# sammy-schematic.net
KiCad netlist of a schematic drawn in EasyEDA
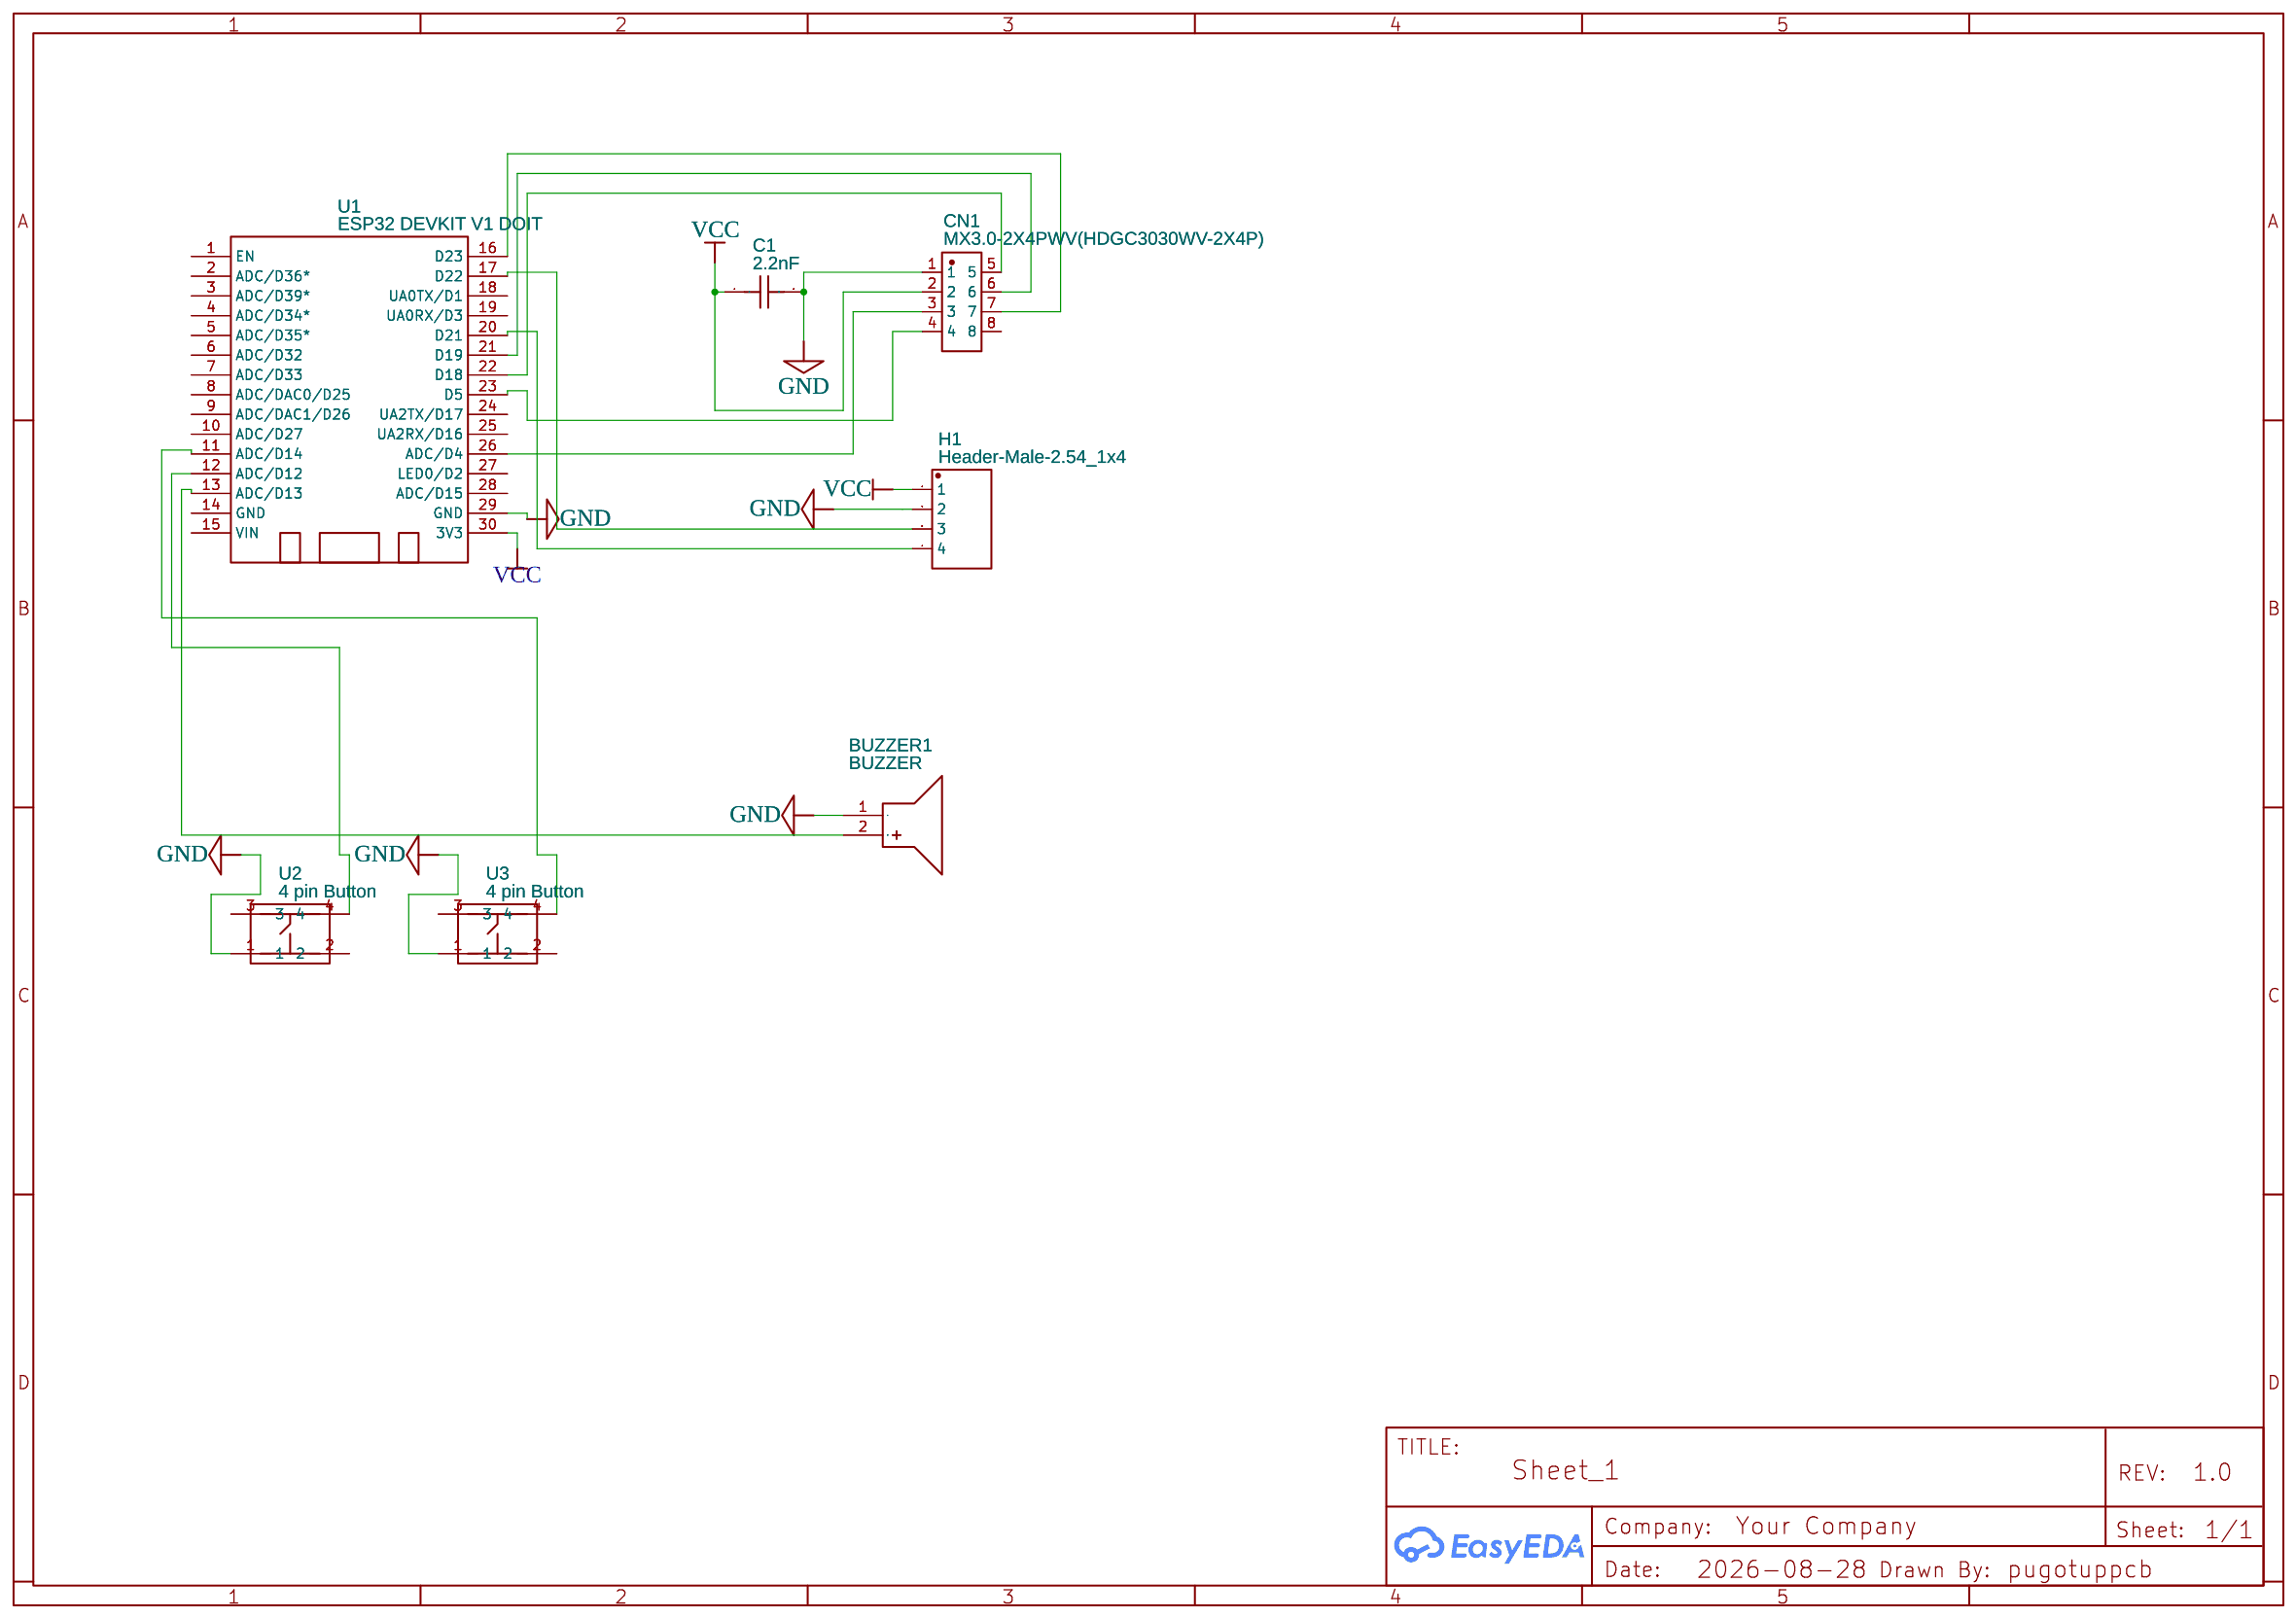
[diagram p0: schematic sheet]

(export (version "E")
  (design (tool "Eeschema 10.0.6"))
  (components
    (comp (ref "BUZZER1")
      (value "BUZZER")
      (fields (field (name "Manufacturer Part") "buzzer"))
      (libsource (lib "") (part "BUZZER"))
    )
    (comp (ref "C1")
      (value "2.2nF")
      (fields (field (name "Manufacturer Part") "C320C222F1G5TA") (field (name "Manufacturer") "KEMET(基美)"))
      (libsource (lib "") (part "C320C222F1G5TA"))
    )
    (comp (ref "CN1")
      (value "MX3.0-2X4PWV(HDGC3030WV-2X4P)")
      (fields (field (name "Manufacturer") "HDGC(华德共创)"))
      (libsource (lib "") (part "MX3.0-2X4PWV(HDGC3030WV-2X4P)"))
    )
    (comp (ref "H1")
      (value "Header-Male-2.54_1x4")
      (fields (field (name "Manufacturer Part") "B-2100S04P-A110") (field (name "Manufacturer") "Ckmtw(灿科盟)"))
      (libsource (lib "") (part "Header-Male-2.54_1x4"))
    )
    (comp (ref "U1") (value "ESP32 DEVKIT V1 DOIT") (libsource (lib "") (part "ESP32 DEVKIT V1 DOIT")))
    (comp (ref "U2") (value "4 pin Button") (libsource (lib "") (part "4 pin Button")))
    (comp (ref "U3") (value "4 pin Button") (libsource (lib "") (part "4 pin Button")))
  )
  (nets
    (net (code "1") (name "GND") (class "Default")
      (node (ref "BUZZER1") (pin "1") (pinfunction "-_1") (pintype "unspecified"))
      (node (ref "C1") (pin "2") (pinfunction "2_2") (pintype "unspecified"))
      (node (ref "CN1") (pin "1") (pinfunction "1_1") (pintype "unspecified"))
      (node (ref "H1") (pin "2") (pinfunction "2_2") (pintype "unspecified"))
      (node (ref "U1") (pin "29") (pinfunction "GND_29") (pintype "bidirectional"))
      (node (ref "U2") (pin "1") (pinfunction "1_1") (pintype "unspecified"))
      (node (ref "U3") (pin "1") (pinfunction "1_1") (pintype "unspecified"))
    )
    (net (code "2") (name "Net-(BUZZER1-+)") (class "Default")
      (node (ref "BUZZER1") (pin "2") (pinfunction "+_2") (pintype "unspecified"))
      (node (ref "U1") (pin "13") (pinfunction "ADC/D13_13") (pintype "bidirectional"))
    )
    (net (code "3") (name "Net-(U1-ADC{slash}D4)") (class "Default")
      (node (ref "CN1") (pin "3") (pinfunction "3_3") (pintype "unspecified"))
      (node (ref "U1") (pin "26") (pinfunction "ADC/D4_26") (pintype "bidirectional"))
    )
    (net (code "4") (name "Net-(U1-ADC{slash}D12)") (class "Default")
      (node (ref "U1") (pin "12") (pinfunction "ADC/D12_12") (pintype "bidirectional"))
      (node (ref "U2") (pin "4") (pinfunction "4_4") (pintype "unspecified"))
    )
    (net (code "5") (name "Net-(U1-ADC{slash}D14)") (class "Default")
      (node (ref "U1") (pin "11") (pinfunction "ADC/D14_11") (pintype "bidirectional"))
      (node (ref "U3") (pin "4") (pinfunction "4_4") (pintype "unspecified"))
    )
    (net (code "6") (name "Net-(U1-D5)") (class "Default")
      (node (ref "CN1") (pin "4") (pinfunction "4_4") (pintype "unspecified"))
      (node (ref "U1") (pin "23") (pinfunction "D5_23") (pintype "bidirectional"))
    )
    (net (code "7") (name "Net-(U1-D18)") (class "Default")
      (node (ref "CN1") (pin "5") (pinfunction "5_5") (pintype "unspecified"))
      (node (ref "U1") (pin "22") (pinfunction "D18_22") (pintype "bidirectional"))
    )
    (net (code "8") (name "Net-(U1-D19)") (class "Default")
      (node (ref "CN1") (pin "6") (pinfunction "6_6") (pintype "unspecified"))
      (node (ref "U1") (pin "21") (pinfunction "D19_21") (pintype "bidirectional"))
    )
    (net (code "9") (name "Net-(U1-D21)") (class "Default")
      (node (ref "H1") (pin "4") (pinfunction "4_4") (pintype "unspecified"))
      (node (ref "U1") (pin "20") (pinfunction "D21_20") (pintype "bidirectional"))
    )
    (net (code "10") (name "Net-(U1-D22)") (class "Default")
      (node (ref "H1") (pin "3") (pinfunction "3_3") (pintype "unspecified"))
      (node (ref "U1") (pin "17") (pinfunction "D22_17") (pintype "bidirectional"))
    )
    (net (code "11") (name "Net-(U1-D23)") (class "Default")
      (node (ref "CN1") (pin "7") (pinfunction "7_7") (pintype "unspecified"))
      (node (ref "U1") (pin "16") (pinfunction "D23_16") (pintype "bidirectional"))
    )
    (net (code "12") (name "VCC") (class "Default")
      (node (ref "C1") (pin "1") (pinfunction "1_1") (pintype "unspecified"))
      (node (ref "CN1") (pin "2") (pinfunction "2_2") (pintype "unspecified"))
      (node (ref "H1") (pin "1") (pinfunction "1_1") (pintype "unspecified"))
      (node (ref "U1") (pin "30") (pinfunction "3V3_30") (pintype "bidirectional"))
    )
    (net (code "13") (name "unconnected-(CN1-Pad8)") (class "Default")
      (node (ref "CN1") (pin "8") (pinfunction "8_8") (pintype "unspecified"))
    )
    (net (code "14") (name "unconnected-(U1-ADC{slash}D15-Pad28)") (class "Default")
      (node (ref "U1") (pin "28") (pinfunction "ADC/D15_28") (pintype "bidirectional"))
    )
    (net (code "15") (name "unconnected-(U1-ADC{slash}D27-Pad10)") (class "Default")
      (node (ref "U1") (pin "10") (pinfunction "ADC/D27_10") (pintype "bidirectional"))
    )
    (net (code "16") (name "unconnected-(U1-ADC{slash}D32-Pad6)") (class "Default")
      (node (ref "U1") (pin "6") (pinfunction "ADC/D32_6") (pintype "bidirectional"))
    )
    (net (code "17") (name "unconnected-(U1-ADC{slash}D33-Pad7)") (class "Default")
      (node (ref "U1") (pin "7") (pinfunction "ADC/D33_7") (pintype "bidirectional"))
    )
    (net (code "18") (name "unconnected-(U1-ADC{slash}D34*-Pad4)") (class "Default")
      (node (ref "U1") (pin "4") (pinfunction "ADC/D34*_4") (pintype "input"))
    )
    (net (code "19") (name "unconnected-(U1-ADC{slash}D35*-Pad5)") (class "Default")
      (node (ref "U1") (pin "5") (pinfunction "ADC/D35*_5") (pintype "input"))
    )
    (net (code "20") (name "unconnected-(U1-ADC{slash}D36*-Pad2)") (class "Default")
      (node (ref "U1") (pin "2") (pinfunction "ADC/D36*_2") (pintype "input"))
    )
    (net (code "21") (name "unconnected-(U1-ADC{slash}D39*-Pad3)") (class "Default")
      (node (ref "U1") (pin "3") (pinfunction "ADC/D39*_3") (pintype "input"))
    )
    (net (code "22") (name "unconnected-(U1-ADC{slash}DAC0{slash}D25-Pad8)") (class "Default")
      (node (ref "U1") (pin "8") (pinfunction "ADC/DAC0/D25_8") (pintype "bidirectional"))
    )
    (net (code "23") (name "unconnected-(U1-ADC{slash}DAC1{slash}D26-Pad9)") (class "Default")
      (node (ref "U1") (pin "9") (pinfunction "ADC/DAC1/D26_9") (pintype "bidirectional"))
    )
    (net (code "24") (name "unconnected-(U1-EN-Pad1)") (class "Default")
      (node (ref "U1") (pin "1") (pinfunction "EN_1") (pintype "bidirectional"))
    )
    (net (code "25") (name "unconnected-(U1-GND-Pad14)") (class "Default")
      (node (ref "U1") (pin "14") (pinfunction "GND_14") (pintype "bidirectional"))
    )
    (net (code "26") (name "unconnected-(U1-LED0{slash}D2-Pad27)") (class "Default")
      (node (ref "U1") (pin "27") (pinfunction "LED0/D2_27") (pintype "bidirectional"))
    )
    (net (code "27") (name "unconnected-(U1-UA0RX{slash}D3-Pad19)") (class "Default")
      (node (ref "U1") (pin "19") (pinfunction "UA0RX/D3_19") (pintype "bidirectional"))
    )
    (net (code "28") (name "unconnected-(U1-UA0TX{slash}D1-Pad18)") (class "Default")
      (node (ref "U1") (pin "18") (pinfunction "UA0TX/D1_18") (pintype "bidirectional"))
    )
    (net (code "29") (name "unconnected-(U1-UA2RX{slash}D16-Pad25)") (class "Default")
      (node (ref "U1") (pin "25") (pinfunction "UA2RX/D16_25") (pintype "bidirectional"))
    )
    (net (code "30") (name "unconnected-(U1-UA2TX{slash}D17-Pad24)") (class "Default")
      (node (ref "U1") (pin "24") (pinfunction "UA2TX/D17_24") (pintype "bidirectional"))
    )
    (net (code "31") (name "unconnected-(U1-VIN-Pad15)") (class "Default")
      (node (ref "U1") (pin "15") (pinfunction "VIN_15") (pintype "input"))
    )
    (net (code "32") (name "unconnected-(U2-Pad2)") (class "Default")
      (node (ref "U2") (pin "2") (pinfunction "2_2") (pintype "unspecified"))
    )
    (net (code "33") (name "unconnected-(U2-Pad3)") (class "Default")
      (node (ref "U2") (pin "3") (pinfunction "3_3") (pintype "unspecified"))
    )
    (net (code "34") (name "unconnected-(U3-Pad2)") (class "Default")
      (node (ref "U3") (pin "2") (pinfunction "2_2") (pintype "unspecified"))
    )
    (net (code "35") (name "unconnected-(U3-Pad3)") (class "Default")
      (node (ref "U3") (pin "3") (pinfunction "3_3") (pintype "unspecified"))
    )
  )
)
